# Microcontroller.net
KiCad netlist of a schematic drawn in Altium Designer
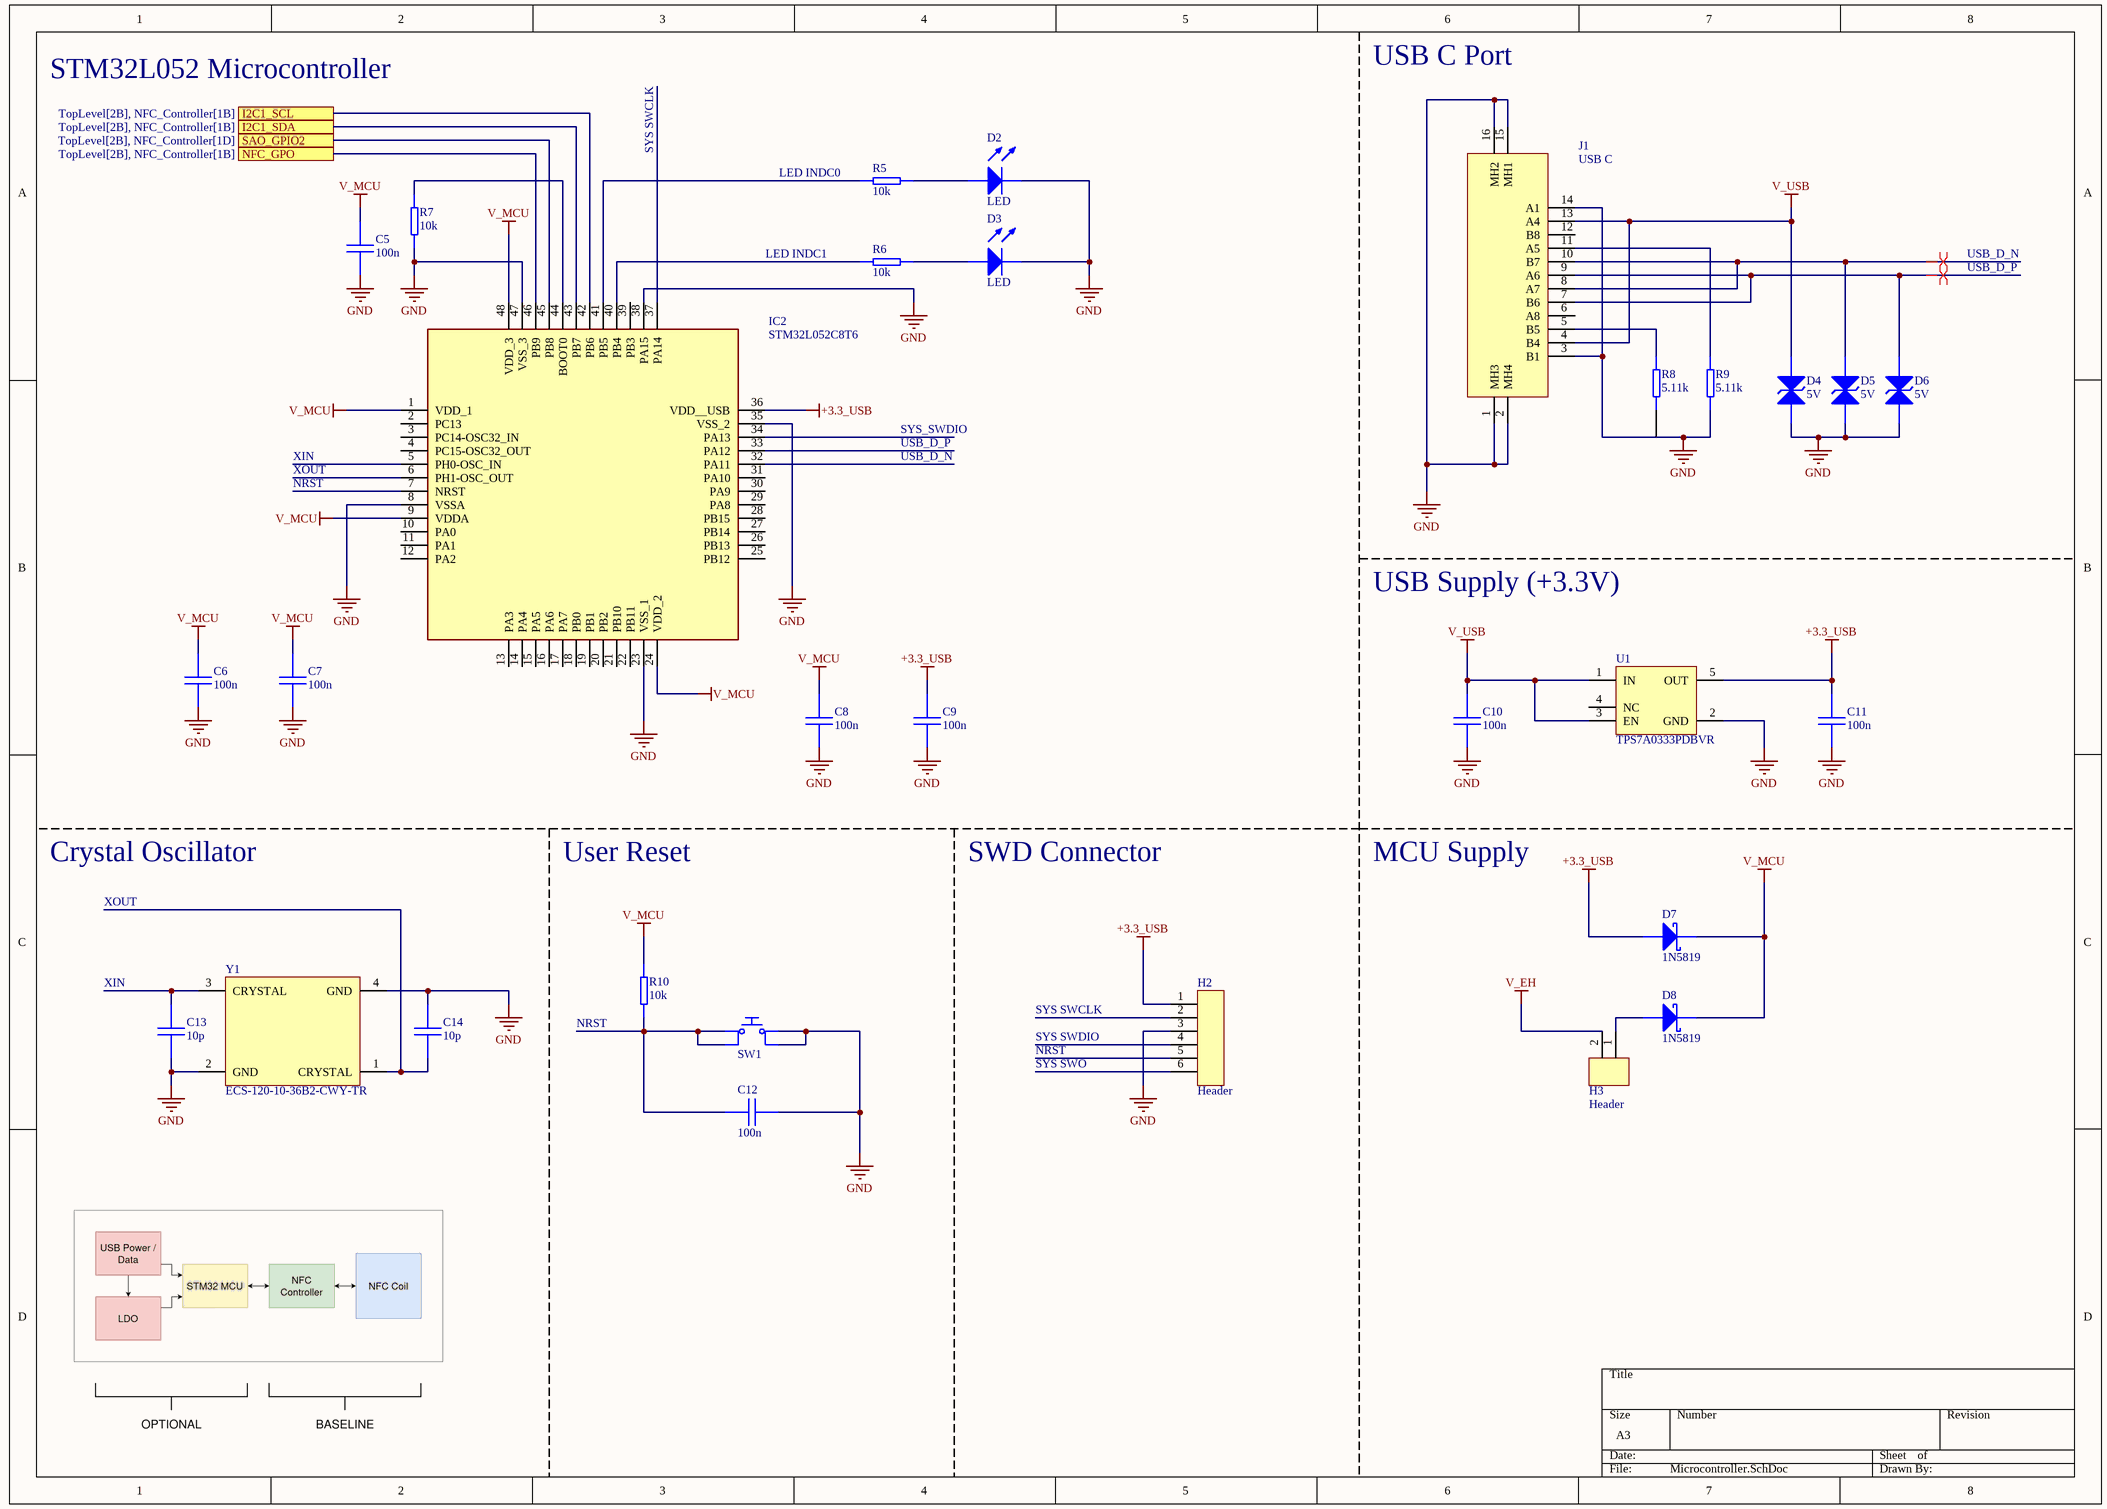
[diagram p0: Microcontroller.SchDoc]

(export (version "E")
  (design (tool "Eeschema 10.0.6"))
  (components
    (comp (ref "C5")
      (value "100n")
      (footprint "CAP0805")
      (description "Non Polarized Capacitor")
      (libsource (lib "NFC_Luggage_Tag") (part "Capacitor - Non Polarized_2"))
    )
    (comp (ref "C6")
      (value "100n")
      (footprint "CAP0805")
      (description "Non Polarized Capacitor")
      (libsource (lib "NFC_Luggage_Tag") (part "Capacitor - Non Polarized_2"))
    )
    (comp (ref "C7")
      (value "100n")
      (footprint "CAP0805")
      (description "Non Polarized Capacitor")
      (libsource (lib "NFC_Luggage_Tag") (part "Capacitor - Non Polarized_2"))
    )
    (comp (ref "C8")
      (value "100n")
      (footprint "CAP0805")
      (description "Non Polarized Capacitor")
      (libsource (lib "NFC_Luggage_Tag") (part "Capacitor - Non Polarized_2"))
    )
    (comp (ref "C9")
      (value "100n")
      (footprint "CAP0805")
      (description "Non Polarized Capacitor")
      (libsource (lib "NFC_Luggage_Tag") (part "Capacitor - Non Polarized_2"))
    )
    (comp (ref "C10")
      (value "100n")
      (footprint "CAP0805")
      (description "Non Polarized Capacitor")
      (libsource (lib "NFC_Luggage_Tag") (part "Capacitor - Non Polarized_2"))
    )
    (comp (ref "C11")
      (value "100n")
      (footprint "CAP0805")
      (description "Non Polarized Capacitor")
      (libsource (lib "NFC_Luggage_Tag") (part "Capacitor - Non Polarized_2"))
    )
    (comp (ref "C12")
      (value "100n")
      (footprint "CAP0805")
      (description "Non Polarized Capacitor")
      (libsource (lib "NFC_Luggage_Tag") (part "Capacitor - Non Polarized"))
    )
    (comp (ref "C13")
      (value "10p")
      (footprint "CAP0402")
      (description "Non Polarized Capacitor")
      (libsource (lib "NFC_Luggage_Tag") (part "Capacitor - Non Polarized_1"))
    )
    (comp (ref "C14")
      (value "10p")
      (footprint "CAP0402")
      (description "Non Polarized Capacitor")
      (libsource (lib "NFC_Luggage_Tag") (part "Capacitor - Non Polarized_1"))
    )
    (comp (ref "D2")
      (value "LED")
      (footprint "LEDM2012X80N")
      (description "General Purpose LED")
      (libsource (lib "NFC_Luggage_Tag") (part "LED"))
    )
    (comp (ref "D3")
      (value "LED")
      (footprint "LEDM2012X80N")
      (description "General Purpose LED")
      (libsource (lib "NFC_Luggage_Tag") (part "LED"))
    )
    (comp (ref "D4")
      (value "5V")
      (footprint "SOD323")
      (description "TVS Diode")
      (libsource (lib "NFC_Luggage_Tag") (part "TVS Diode"))
    )
    (comp (ref "D5")
      (value "5V")
      (footprint "SOD323")
      (description "TVS Diode")
      (libsource (lib "NFC_Luggage_Tag") (part "TVS Diode"))
    )
    (comp (ref "D6")
      (value "5V")
      (footprint "SOD323")
      (description "TVS Diode")
      (libsource (lib "NFC_Luggage_Tag") (part "TVS Diode"))
    )
    (comp (ref "D7")
      (value "1N5819")
      (footprint "SOD323")
      (description "1N5819 Schottkey Diode")
      (libsource (lib "NFC_Luggage_Tag") (part "1N5819"))
    )
    (comp (ref "D8")
      (value "1N5819")
      (footprint "SOD323")
      (description "1N5819 Schottkey Diode")
      (libsource (lib "NFC_Luggage_Tag") (part "1N5819"))
    )
    (comp (ref "H2")
      (value "Header")
      (footprint "Header_1X6")
      (description "6-Pin Header")
      (libsource (lib "NFC_Luggage_Tag") (part "6-Pin Header"))
    )
    (comp (ref "H3")
      (value "Header")
      (footprint "Header_1X2")
      (description "2-Pin Header")
      (libsource (lib "NFC_Luggage_Tag") (part "2-Pin Header"))
    )
    (comp (ref "IC2")
      (value "STM32L052C8T6")
      (footprint "QFP50P900X900X160-48N")
      (description "Integrated Circuit")
      (fields (field (name "MOUSER PART NUMBER") "511-STM32L052C8T6"))
      (libsource (lib "NFC_Luggage_Tag") (part "STM32L052C8T6"))
    )
    (comp (ref "J1")
      (value "USB C")
      (footprint "USB TYPE C 12 PIN")
      (libsource (lib "NFC_Luggage_Tag") (part "USB Type C Connector 12 Pin"))
    )
    (comp (ref "R5")
      (value "10k")
      (footprint "RESC0805")
      (description "Resistor")
      (libsource (lib "NFC_Luggage_Tag") (part "Resistor"))
    )
    (comp (ref "R6")
      (value "10k")
      (footprint "RESC0805")
      (description "Resistor")
      (libsource (lib "NFC_Luggage_Tag") (part "Resistor"))
    )
    (comp (ref "R7")
      (value "10k")
      (footprint "RESC0805")
      (description "Resistor")
      (libsource (lib "NFC_Luggage_Tag") (part "Resistor_2"))
    )
    (comp (ref "R8")
      (value "5.11k")
      (footprint "RESC0805")
      (description "Resistor")
      (libsource (lib "NFC_Luggage_Tag") (part "Resistor_1"))
    )
    (comp (ref "R9")
      (value "5.11k")
      (footprint "RESC0805")
      (description "Resistor")
      (libsource (lib "NFC_Luggage_Tag") (part "Resistor_1"))
    )
    (comp (ref "R10")
      (value "10k")
      (footprint "RESC0805")
      (description "Resistor")
      (libsource (lib "NFC_Luggage_Tag") (part "Resistor"))
    )
    (comp (ref "SW1")
      (value "Tactile Switch - 1")
      (footprint "Tactile Button 4.2mm x 3.2mm")
      (description "Tactile Pushbutton - Contact Pad")
      (libsource (lib "NFC_Luggage_Tag") (part "Tactile Switch - 1"))
    )
    (comp (ref "U1")
      (value "TPS7A0333PDBVR")
      (footprint "SOT23-5")
      (fields (field (name "MOUSER PART NUMBER") "595-TPS7A0333PDBVR"))
      (libsource (lib "NFC_Luggage_Tag") (part "TPS7A0333PDBVR"))
    )
    (comp (ref "Y1")
      (value "ECS-120-10-36B2-CWY-TR")
      (footprint "TD:ECS1201036B2CWYTR")
      (description "Crystal or Oscillator")
      (fields (field (name "MOUSER PART NUMBER") "520-120-10-36B2CWYTR"))
      (libsource (lib "NFC_Luggage_Tag") (part "ECS-120-10-36B2-CWY-TR"))
    )
  )
  (nets
    (net (code "1") (name "+3.3_USB") (class "Default")
      (node (ref "C11") (pin "1") (pintype "passive"))
      (node (ref "C9") (pin "1") (pintype "passive"))
      (node (ref "D7") (pin "2") (pinfunction "A_2") (pintype "passive"))
      (node (ref "H2") (pin "1") (pintype "passive"))
      (node (ref "IC2") (pin "36") (pinfunction "VDD__USB_36") (pintype "passive"))
      (node (ref "U1") (pin "5") (pinfunction "OUT_5") (pintype "passive"))
    )
    (net (code "2") (name "/I2C1_SCL") (class "Default")
      (node (ref "IC2") (pin "42") (pinfunction "PB6_42") (pintype "passive"))
    )
    (net (code "3") (name "/I2C1_SDA") (class "Default")
      (node (ref "IC2") (pin "43") (pinfunction "PB7_43") (pintype "passive"))
    )
    (net (code "4") (name "/NFC_GPO") (class "Default")
      (node (ref "IC2") (pin "46") (pinfunction "PB9_46") (pintype "passive"))
    )
    (net (code "5") (name "/SAO_GPIO2") (class "Default")
      (node (ref "IC2") (pin "45") (pinfunction "PB8_45") (pintype "passive"))
    )
    (net (code "6") (name "GND") (class "Default")
      (node (ref "C10") (pin "2") (pintype "passive"))
      (node (ref "C11") (pin "2") (pintype "passive"))
      (node (ref "C12") (pin "2") (pintype "passive"))
      (node (ref "C13") (pin "2") (pintype "passive"))
      (node (ref "C14") (pin "1") (pintype "passive"))
      (node (ref "C5") (pin "2") (pintype "passive"))
      (node (ref "C6") (pin "2") (pintype "passive"))
      (node (ref "C7") (pin "2") (pintype "passive"))
      (node (ref "C8") (pin "2") (pintype "passive"))
      (node (ref "C9") (pin "2") (pintype "passive"))
      (node (ref "D2") (pin "1") (pinfunction "K_1") (pintype "passive"))
      (node (ref "D3") (pin "1") (pinfunction "K_1") (pintype "passive"))
      (node (ref "D4") (pin "1") (pinfunction "A_1") (pintype "passive"))
      (node (ref "D5") (pin "1") (pinfunction "A_1") (pintype "passive"))
      (node (ref "D6") (pin "1") (pinfunction "A_1") (pintype "passive"))
      (node (ref "H2") (pin "3") (pintype "passive"))
      (node (ref "IC2") (pin "23") (pinfunction "VSS_1_23") (pintype "passive"))
      (node (ref "IC2") (pin "35") (pinfunction "VSS_2_35") (pintype "passive"))
      (node (ref "IC2") (pin "38") (pinfunction "PA15_38") (pintype "passive"))
      (node (ref "IC2") (pin "47") (pinfunction "VSS_3_47") (pintype "passive"))
      (node (ref "IC2") (pin "8") (pinfunction "VSSA_8") (pintype "passive"))
      (node (ref "J1") (pin "1") (pinfunction "MH3_1") (pintype "passive"))
      (node (ref "J1") (pin "14") (pinfunction "A1_14") (pintype "passive"))
      (node (ref "J1") (pin "15") (pinfunction "MH1_15") (pintype "passive"))
      (node (ref "J1") (pin "16") (pinfunction "MH2_16") (pintype "passive"))
      (node (ref "J1") (pin "2") (pinfunction "MH4_2") (pintype "passive"))
      (node (ref "J1") (pin "3") (pinfunction "B1_3") (pintype "passive"))
      (node (ref "R7") (pin "2") (pintype "passive"))
      (node (ref "R9") (pin "2") (pintype "passive"))
      (node (ref "SW1") (pin "3") (pintype "passive"))
      (node (ref "SW1") (pin "4") (pintype "passive"))
      (node (ref "U1") (pin "2") (pinfunction "GND_2") (pintype "passive"))
      (node (ref "Y1") (pin "2") (pinfunction "GND_2") (pintype "passive"))
      (node (ref "Y1") (pin "4") (pinfunction "GND_4") (pintype "passive"))
    )
    (net (code "7") (name "Net-(C12-Pad1)") (class "Default")
      (node (ref "C12") (pin "1") (pintype "passive"))
      (node (ref "R10") (pin "2") (pintype "passive"))
      (node (ref "SW1") (pin "1") (pintype "passive"))
      (node (ref "SW1") (pin "2") (pintype "passive"))
    )
    (net (code "8") (name "Net-(C13-Pad1)") (class "Default")
      (node (ref "C13") (pin "1") (pintype "passive"))
      (node (ref "Y1") (pin "3") (pinfunction "CRYSTAL_3") (pintype "passive"))
    )
    (net (code "9") (name "Net-(C14-Pad2)") (class "Default")
      (node (ref "C14") (pin "2") (pintype "passive"))
      (node (ref "Y1") (pin "1") (pinfunction "CRYSTAL_1") (pintype "passive"))
    )
    (net (code "10") (name "Net-(D2-A)") (class "Default")
      (node (ref "D2") (pin "2") (pinfunction "A_2") (pintype "passive"))
      (node (ref "R5") (pin "2") (pintype "passive"))
    )
    (net (code "11") (name "Net-(D3-A)") (class "Default")
      (node (ref "D3") (pin "2") (pinfunction "A_2") (pintype "passive"))
      (node (ref "R6") (pin "2") (pintype "passive"))
    )
    (net (code "12") (name "Net-(D5-K)") (class "Default")
      (node (ref "D5") (pin "2") (pinfunction "K_2") (pintype "passive"))
      (node (ref "J1") (pin "10") (pinfunction "B7_10") (pintype "passive"))
      (node (ref "J1") (pin "8") (pinfunction "A7_8") (pintype "passive"))
    )
    (net (code "13") (name "Net-(D6-K)") (class "Default")
      (node (ref "D6") (pin "2") (pinfunction "K_2") (pintype "passive"))
      (node (ref "J1") (pin "7") (pinfunction "B6_7") (pintype "passive"))
      (node (ref "J1") (pin "9") (pinfunction "A6_9") (pintype "passive"))
    )
    (net (code "14") (name "Net-(D8-A)") (class "Default")
      (node (ref "D8") (pin "2") (pinfunction "A_2") (pintype "passive"))
      (node (ref "H3") (pin "1") (pintype "passive"))
    )
    (net (code "15") (name "Net-(IC2-BOOT0)") (class "Default")
      (node (ref "IC2") (pin "44") (pinfunction "BOOT0_44") (pintype "passive"))
      (node (ref "R7") (pin "1") (pintype "passive"))
    )
    (net (code "16") (name "Net-(IC2-PB4)") (class "Default")
      (node (ref "IC2") (pin "40") (pinfunction "PB4_40") (pintype "passive"))
      (node (ref "R6") (pin "1") (pintype "passive"))
    )
    (net (code "17") (name "Net-(IC2-PB5)") (class "Default")
      (node (ref "IC2") (pin "41") (pinfunction "PB5_41") (pintype "passive"))
      (node (ref "R5") (pin "1") (pintype "passive"))
    )
    (net (code "18") (name "Net-(J1-A5)") (class "Default")
      (node (ref "J1") (pin "11") (pinfunction "A5_11") (pintype "passive"))
      (node (ref "R9") (pin "1") (pintype "passive"))
    )
    (net (code "19") (name "Net-(J1-B5)") (class "Default")
      (node (ref "J1") (pin "5") (pinfunction "B5_5") (pintype "passive"))
      (node (ref "R8") (pin "1") (pintype "passive"))
    )
    (net (code "20") (name "V_EH") (class "Default") (node (ref "H3") (pin "2") (pintype "passive")))
    (net (code "21") (name "V_MCU") (class "Default")
      (node (ref "C5") (pin "1") (pintype "passive"))
      (node (ref "C6") (pin "1") (pintype "passive"))
      (node (ref "C7") (pin "1") (pintype "passive"))
      (node (ref "C8") (pin "1") (pintype "passive"))
      (node (ref "D7") (pin "1") (pinfunction "K_1") (pintype "passive"))
      (node (ref "D8") (pin "1") (pinfunction "K_1") (pintype "passive"))
      (node (ref "IC2") (pin "1") (pinfunction "VDD_1_1") (pintype "passive"))
      (node (ref "IC2") (pin "24") (pinfunction "VDD_2_24") (pintype "passive"))
      (node (ref "IC2") (pin "48") (pinfunction "VDD_3_48") (pintype "passive"))
      (node (ref "IC2") (pin "9") (pinfunction "VDDA_9") (pintype "passive"))
      (node (ref "R10") (pin "1") (pintype "passive"))
    )
    (net (code "22") (name "V_USB") (class "Default")
      (node (ref "C10") (pin "1") (pintype "passive"))
      (node (ref "D4") (pin "2") (pinfunction "K_2") (pintype "passive"))
      (node (ref "J1") (pin "13") (pinfunction "A4_13") (pintype "passive"))
      (node (ref "J1") (pin "4") (pinfunction "B4_4") (pintype "passive"))
      (node (ref "U1") (pin "1") (pinfunction "IN_1") (pintype "passive"))
      (node (ref "U1") (pin "3") (pinfunction "EN_3") (pintype "passive"))
    )
    (net (code "23") (name "unconnected-(H2-Pad2)") (class "Default")
      (node (ref "H2") (pin "2") (pintype "passive"))
    )
    (net (code "24") (name "unconnected-(H2-Pad4)") (class "Default")
      (node (ref "H2") (pin "4") (pintype "passive"))
    )
    (net (code "25") (name "unconnected-(H2-Pad5)") (class "Default")
      (node (ref "H2") (pin "5") (pintype "passive"))
    )
    (net (code "26") (name "unconnected-(H2-Pad6)") (class "Default")
      (node (ref "H2") (pin "6") (pintype "passive"))
    )
    (net (code "27") (name "unconnected-(IC2-NRST-Pad7)") (class "Default")
      (node (ref "IC2") (pin "7") (pinfunction "NRST_7") (pintype "passive"))
    )
    (net (code "28") (name "unconnected-(IC2-PA0-Pad10)") (class "Default")
      (node (ref "IC2") (pin "10") (pinfunction "PA0_10") (pintype "passive"))
    )
    (net (code "29") (name "unconnected-(IC2-PA1-Pad11)") (class "Default")
      (node (ref "IC2") (pin "11") (pinfunction "PA1_11") (pintype "passive"))
    )
    (net (code "30") (name "unconnected-(IC2-PA2-Pad12)") (class "Default")
      (node (ref "IC2") (pin "12") (pinfunction "PA2_12") (pintype "passive"))
    )
    (net (code "31") (name "unconnected-(IC2-PA3-Pad13)") (class "Default")
      (node (ref "IC2") (pin "13") (pinfunction "PA3_13") (pintype "passive"))
    )
    (net (code "32") (name "unconnected-(IC2-PA4-Pad14)") (class "Default")
      (node (ref "IC2") (pin "14") (pinfunction "PA4_14") (pintype "passive"))
    )
    (net (code "33") (name "unconnected-(IC2-PA5-Pad15)") (class "Default")
      (node (ref "IC2") (pin "15") (pinfunction "PA5_15") (pintype "passive"))
    )
    (net (code "34") (name "unconnected-(IC2-PA6-Pad16)") (class "Default")
      (node (ref "IC2") (pin "16") (pinfunction "PA6_16") (pintype "passive"))
    )
    (net (code "35") (name "unconnected-(IC2-PA7-Pad17)") (class "Default")
      (node (ref "IC2") (pin "17") (pinfunction "PA7_17") (pintype "passive"))
    )
    (net (code "36") (name "unconnected-(IC2-PA8-Pad29)") (class "Default")
      (node (ref "IC2") (pin "29") (pinfunction "PA8_29") (pintype "passive"))
    )
    (net (code "37") (name "unconnected-(IC2-PA9-Pad30)") (class "Default")
      (node (ref "IC2") (pin "30") (pinfunction "PA9_30") (pintype "passive"))
    )
    (net (code "38") (name "unconnected-(IC2-PA10-Pad31)") (class "Default")
      (node (ref "IC2") (pin "31") (pinfunction "PA10_31") (pintype "passive"))
    )
    (net (code "39") (name "unconnected-(IC2-PA11-Pad32)") (class "Default")
      (node (ref "IC2") (pin "32") (pinfunction "PA11_32") (pintype "passive"))
    )
    (net (code "40") (name "unconnected-(IC2-PA12-Pad33)") (class "Default")
      (node (ref "IC2") (pin "33") (pinfunction "PA12_33") (pintype "passive"))
    )
    (net (code "41") (name "unconnected-(IC2-PA13-Pad34)") (class "Default")
      (node (ref "IC2") (pin "34") (pinfunction "PA13_34") (pintype "passive"))
    )
    (net (code "42") (name "unconnected-(IC2-PA14-Pad37)") (class "Default")
      (node (ref "IC2") (pin "37") (pinfunction "PA14_37") (pintype "passive"))
    )
    (net (code "43") (name "unconnected-(IC2-PB0-Pad18)") (class "Default")
      (node (ref "IC2") (pin "18") (pinfunction "PB0_18") (pintype "passive"))
    )
    (net (code "44") (name "unconnected-(IC2-PB1-Pad19)") (class "Default")
      (node (ref "IC2") (pin "19") (pinfunction "PB1_19") (pintype "passive"))
    )
    (net (code "45") (name "unconnected-(IC2-PB2-Pad20)") (class "Default")
      (node (ref "IC2") (pin "20") (pinfunction "PB2_20") (pintype "passive"))
    )
    (net (code "46") (name "unconnected-(IC2-PB3-Pad39)") (class "Default")
      (node (ref "IC2") (pin "39") (pinfunction "PB3_39") (pintype "passive"))
    )
    (net (code "47") (name "unconnected-(IC2-PB10-Pad21)") (class "Default")
      (node (ref "IC2") (pin "21") (pinfunction "PB10_21") (pintype "passive"))
    )
    (net (code "48") (name "unconnected-(IC2-PB11-Pad22)") (class "Default")
      (node (ref "IC2") (pin "22") (pinfunction "PB11_22") (pintype "passive"))
    )
    (net (code "49") (name "unconnected-(IC2-PB12-Pad25)") (class "Default")
      (node (ref "IC2") (pin "25") (pinfunction "PB12_25") (pintype "passive"))
    )
    (net (code "50") (name "unconnected-(IC2-PB13-Pad26)") (class "Default")
      (node (ref "IC2") (pin "26") (pinfunction "PB13_26") (pintype "passive"))
    )
    (net (code "51") (name "unconnected-(IC2-PB14-Pad27)") (class "Default")
      (node (ref "IC2") (pin "27") (pinfunction "PB14_27") (pintype "passive"))
    )
    (net (code "52") (name "unconnected-(IC2-PB15-Pad28)") (class "Default")
      (node (ref "IC2") (pin "28") (pinfunction "PB15_28") (pintype "passive"))
    )
    (net (code "53") (name "unconnected-(IC2-PC13-Pad2)") (class "Default")
      (node (ref "IC2") (pin "2") (pinfunction "PC13_2") (pintype "passive"))
    )
    (net (code "54") (name "unconnected-(IC2-PC14-OSC32_IN-Pad3)") (class "Default")
      (node (ref "IC2") (pin "3") (pinfunction "PC14-OSC32_IN_3") (pintype "passive"))
    )
    (net (code "55") (name "unconnected-(IC2-PC15-OSC32_OUT-Pad4)") (class "Default")
      (node (ref "IC2") (pin "4") (pinfunction "PC15-OSC32_OUT_4") (pintype "passive"))
    )
    (net (code "56") (name "unconnected-(IC2-PH0-OSC_IN-Pad5)") (class "Default")
      (node (ref "IC2") (pin "5") (pinfunction "PH0-OSC_IN_5") (pintype "passive"))
    )
    (net (code "57") (name "unconnected-(IC2-PH1-OSC_OUT-Pad6)") (class "Default")
      (node (ref "IC2") (pin "6") (pinfunction "PH1-OSC_OUT_6") (pintype "passive"))
    )
    (net (code "58") (name "unconnected-(J1-A8-Pad6)") (class "Default")
      (node (ref "J1") (pin "6") (pinfunction "A8_6") (pintype "passive"))
    )
    (net (code "59") (name "unconnected-(J1-B8-Pad12)") (class "Default")
      (node (ref "J1") (pin "12") (pinfunction "B8_12") (pintype "passive"))
    )
    (net (code "60") (name "unconnected-(R8-Pad2)") (class "Default")
      (node (ref "R8") (pin "2") (pintype "passive"))
    )
    (net (code "61") (name "unconnected-(U1-NC-Pad4)") (class "Default")
      (node (ref "U1") (pin "4") (pinfunction "NC_4") (pintype "passive"))
    )
  )
)
